# ESP32_sparrow.net
KiCad netlist of a schematic drawn in EAGLE
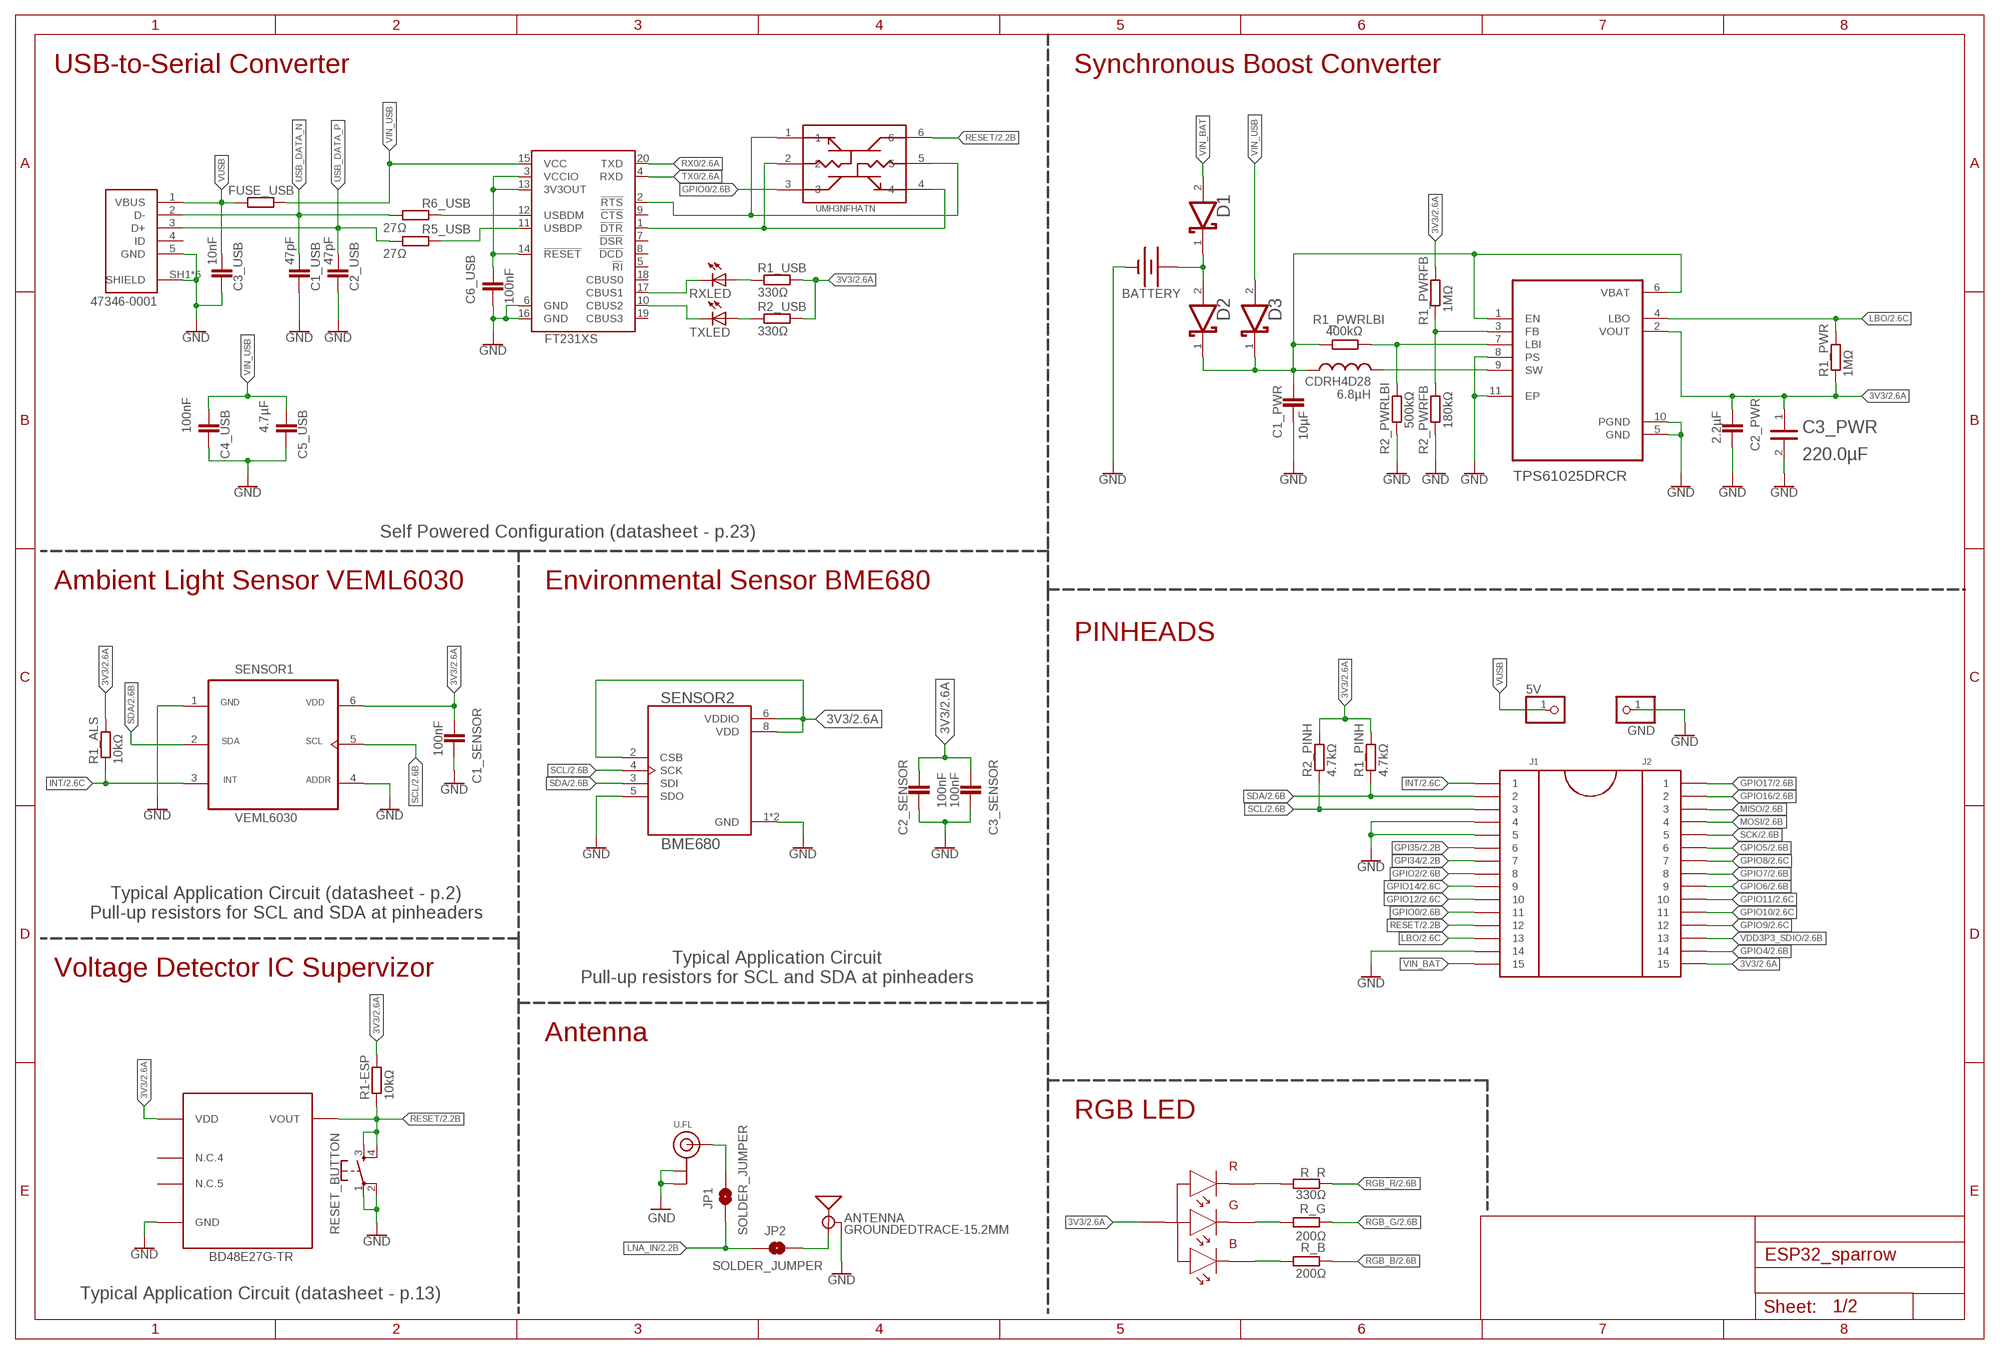
[diagram p0: schematic, sheet 1]
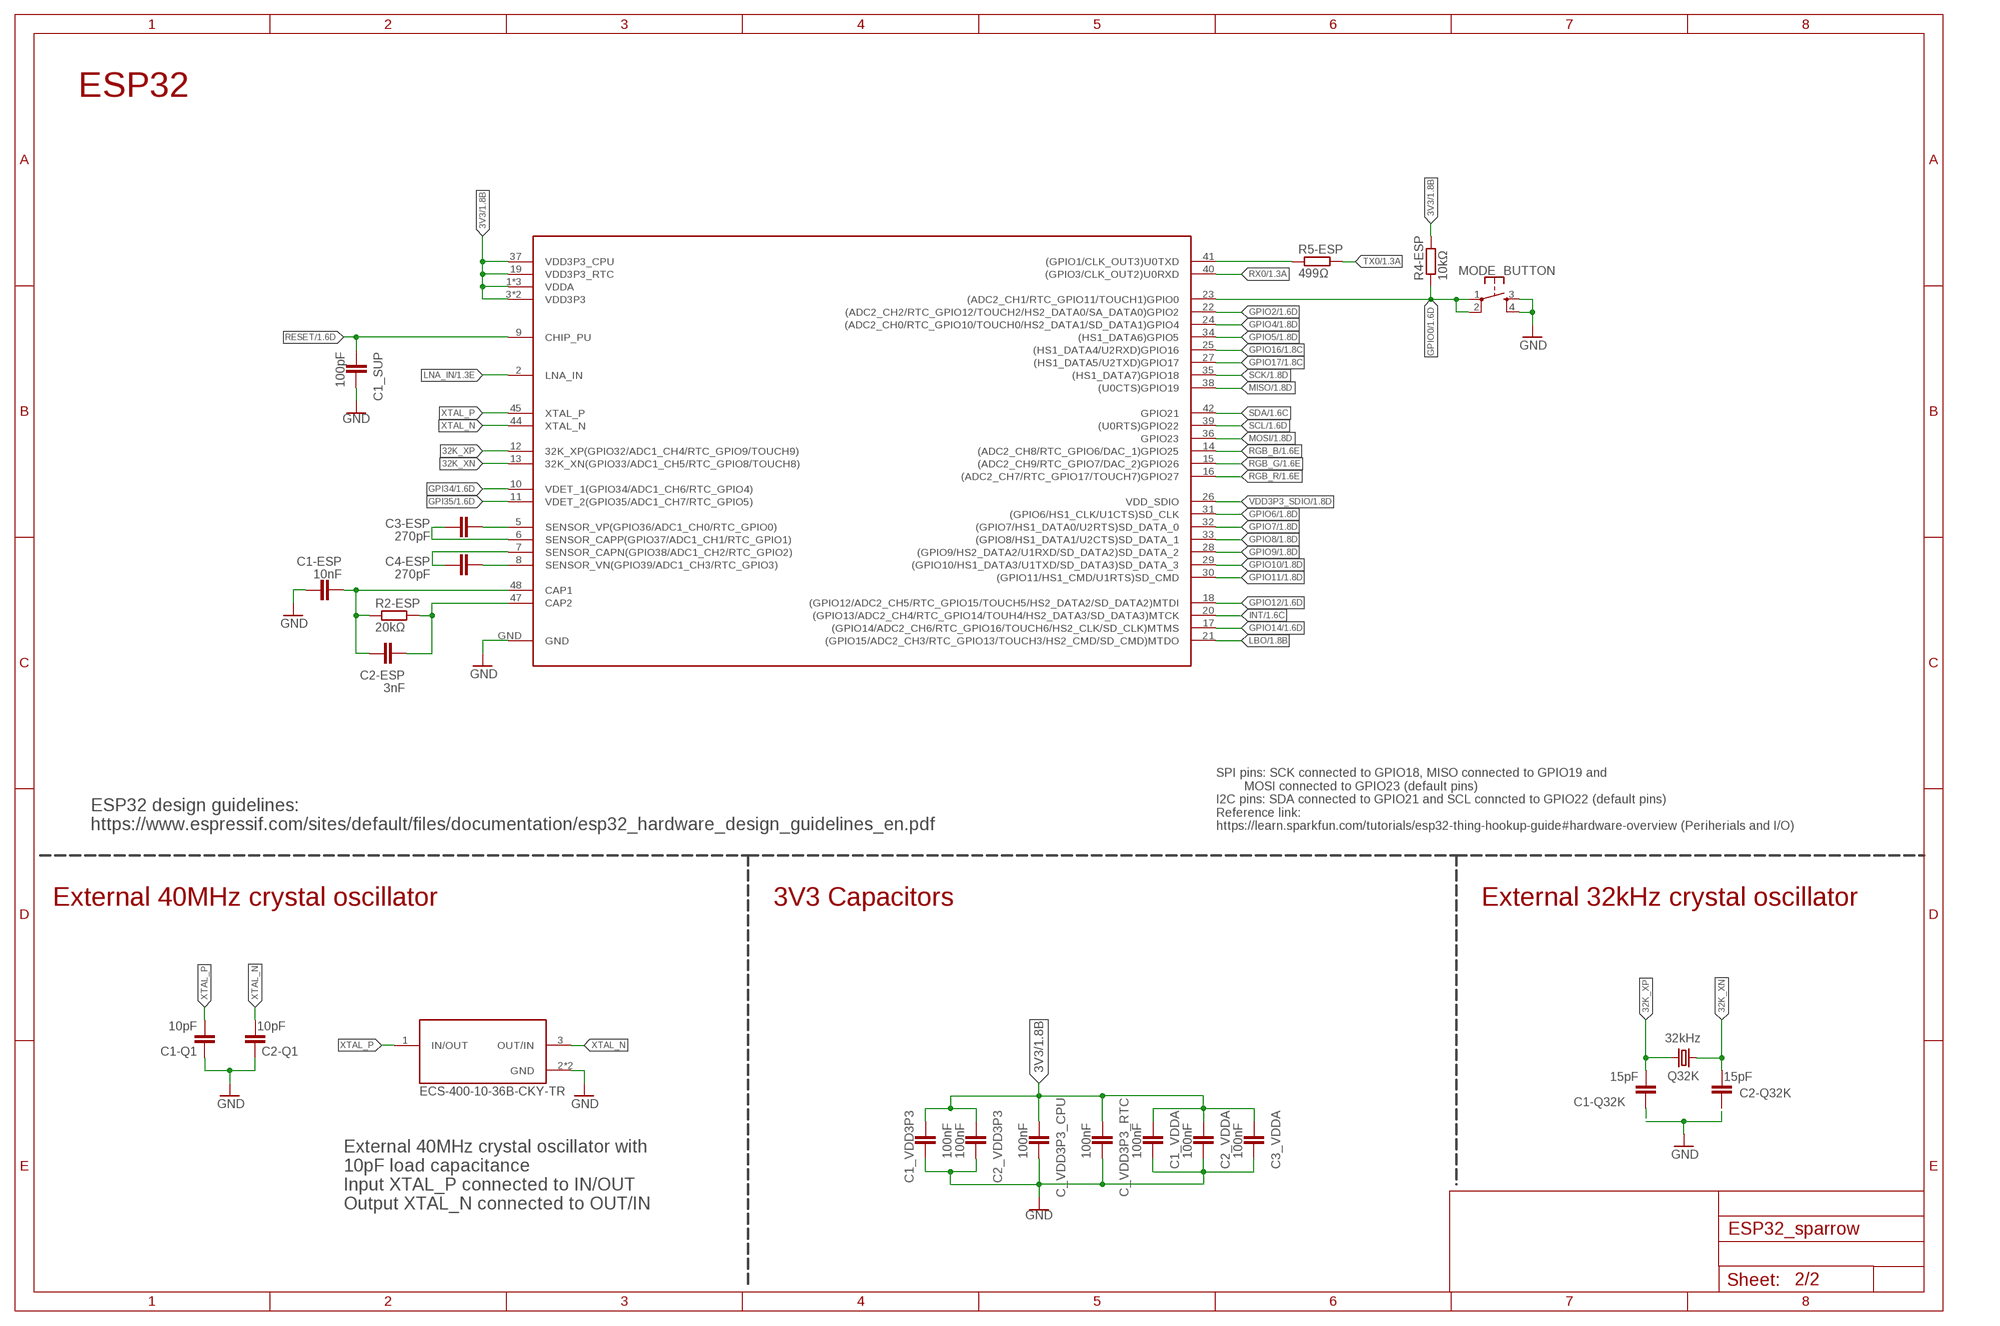
[diagram p1: schematic, sheet 2]

(export (version "E")
  (design (tool "Eeschema 10.0.6"))
  (components
    (comp (ref "C1-ESP")
      (value "10nF")
      (footprint "eagle-import:C0402")
      (libsource (lib "eagle-import") (part "CC0402"))
    )
    (comp (ref "C1-Q1")
      (value "10pF")
      (footprint "eagle-import:C0402")
      (libsource (lib "eagle-import") (part "CC0402"))
    )
    (comp (ref "C1-Q32K")
      (value "15pF")
      (footprint "eagle-import:C0402")
      (libsource (lib "eagle-import") (part "CC0402"))
    )
    (comp (ref "C1_SUP")
      (value "100pF")
      (footprint "eagle-import:C0402")
      (libsource (lib "eagle-import") (part "CC0402"))
    )
    (comp (ref "C1_VDD3P3")
      (value "100nF")
      (footprint "eagle-import:C0402")
      (libsource (lib "eagle-import") (part "CC0402"))
    )
    (comp (ref "C1_VDDA")
      (value "100nF")
      (footprint "eagle-import:C0402")
      (libsource (lib "eagle-import") (part "CC0402"))
    )
    (comp (ref "C2-ESP")
      (value "3nF")
      (footprint "eagle-import:C0402")
      (libsource (lib "eagle-import") (part "CC0402"))
    )
    (comp (ref "C2-Q1")
      (value "10pF")
      (footprint "eagle-import:C0402")
      (libsource (lib "eagle-import") (part "CC0402"))
    )
    (comp (ref "C2-Q32K")
      (value "15pF")
      (footprint "eagle-import:C0402")
      (libsource (lib "eagle-import") (part "CC0402"))
    )
    (comp (ref "C2_VDD3P3")
      (value "100nF")
      (footprint "eagle-import:C0402")
      (libsource (lib "eagle-import") (part "CC0402"))
    )
    (comp (ref "C2_VDDA")
      (value "100nF")
      (footprint "eagle-import:C0402")
      (libsource (lib "eagle-import") (part "CC0402"))
    )
    (comp (ref "C3-ESP")
      (value "270pF")
      (footprint "eagle-import:C0402")
      (libsource (lib "eagle-import") (part "CC0402"))
    )
    (comp (ref "C3_VDDA")
      (value "100nF")
      (footprint "eagle-import:C0402")
      (libsource (lib "eagle-import") (part "CC0402"))
    )
    (comp (ref "C4-ESP")
      (value "270pF")
      (footprint "eagle-import:C0402")
      (libsource (lib "eagle-import") (part "CC0402"))
    )
    (comp (ref "C_VDD3P3_CPU")
      (value "100nF")
      (footprint "eagle-import:C0402")
      (libsource (lib "eagle-import") (part "CC0402"))
    )
    (comp (ref "C_VDD3P3_RTC")
      (value "100nF")
      (footprint "eagle-import:C0402")
      (libsource (lib "eagle-import") (part "CC0402"))
    )
    (comp (ref "MODE_BUTTON")
      (value "MOMENTARY-SWITCH-SPST-2-SMD-4.6X2.8MM")
      (footprint "eagle-import:TACTILE_SWITCH_SMD_4.6X2.8MM")
      (libsource (lib "eagle-import") (part "MOMENTARY-SWITCH-SPST-2-SMD-4.6X2.8MM"))
    )
    (comp (ref "Q32K")
      (value "32kHz")
      (footprint "eagle-import:FC-12M")
      (libsource (lib "eagle-import") (part "FC-12M"))
    )
    (comp (ref "Q40M")
      (value "ECS-400-10-36B-CKY-TR")
      (footprint "eagle-import:XTAL_ECS-163.84-10-36-JGN-TR")
      (fields (field (name "MF") "ECS Inc."))
      (libsource (lib "eagle-import") (part "ECS-400-10-36B-CKY-TR"))
    )
    (comp (ref "R2-ESP")
      (value "20kΩ")
      (footprint "eagle-import:R0402")
      (libsource (lib "eagle-import") (part "RR0402"))
    )
    (comp (ref "R4-ESP")
      (value "10kΩ")
      (footprint "eagle-import:R0402")
      (libsource (lib "eagle-import") (part "RR0402"))
    )
    (comp (ref "R5-ESP")
      (value "499Ω")
      (footprint "eagle-import:R0402")
      (libsource (lib "eagle-import") (part "RR0402"))
    )
    (comp (ref "U$3")
      (value "ESP32-U4WDH")
      (footprint "eagle-import:ESP32-U4WDH")
      (libsource (lib "eagle-import") (part "ESP32-U4WDH"))
    )
    (comp (ref "5V")
      (value "PINHD-1X1")
      (footprint "eagle-import:1X01")
      (libsource (lib "eagle-import") (part "PINHD-1X1"))
    )
    (comp (ref "ANTENNA")
      (value "GROUNDEDTRACE-15.2MM")
      (footprint "eagle-import:TRACE_ANTENNA_2.4GHZ_15.2MM")
      (libsource (lib "eagle-import") (part "ANTENNA-GROUNDEDTRACE-15.2MM"))
    )
    (comp (ref "BATTERY")
      (value "BATTERY-AA")
      (footprint "eagle-import:BATTERY-AA")
      (libsource (lib "eagle-import") (part "BATTERY-AA"))
    )
    (comp (ref "BD48E27G-TR")
      (value "BD48E27G-TR")
      (footprint "eagle-import:SSOP5")
      (libsource (lib "eagle-import") (part "BD48E27G-TR"))
    )
    (comp (ref "C1_PWR")
      (value "10µF")
      (footprint "eagle-import:C0402")
      (libsource (lib "eagle-import") (part "CC0402"))
    )
    (comp (ref "C1_SENSOR")
      (value "100nF")
      (footprint "eagle-import:C0402")
      (libsource (lib "eagle-import") (part "CC0402"))
    )
    (comp (ref "C1_USB")
      (value "47pF")
      (footprint "eagle-import:C0402")
      (libsource (lib "eagle-import") (part "CC0402"))
    )
    (comp (ref "C2_PWR")
      (value "2.2µF")
      (footprint "eagle-import:C0402")
      (libsource (lib "eagle-import") (part "CC0402"))
    )
    (comp (ref "C2_SENSOR")
      (value "100nF")
      (footprint "eagle-import:C0402")
      (libsource (lib "eagle-import") (part "CC0402"))
    )
    (comp (ref "C2_USB")
      (value "47pF")
      (footprint "eagle-import:C0402")
      (libsource (lib "eagle-import") (part "CC0402"))
    )
    (comp (ref "C3_PWR")
      (value "SAMSUNG_ELECTRO-MECHANICS_AMERICA_CL32A227MQVNNNESAMSUNG_ELECTRO-MECHANICS_AMERICA_CL32A227MQVNNNE_0_0")
      (footprint "eagle-import:SAMSUNG_ELECTRO-MECHANICS_AMERICA_CL32A227MQVNNNE_0")
      (fields
        (field (name "DIGIKEY_PART_NUMBER") "1276-3375-1-ND")
        (field (name "MF") "Samsung Electro-Mechanics America")
        (field (name "MPN") "CL32A227MQVNNNE")
      )
      (libsource (lib "eagle-import") (part "SAMSUNG_ELECTRO-MECHANICS_AMERICA_CL32A227MQVNNNESAMSUNG_ELECTRO-MECHANICS_AMERICA_CL32A227MQVNNNE_0_0"))
    )
    (comp (ref "C3_SENSOR")
      (value "100nF")
      (footprint "eagle-import:C0402")
      (libsource (lib "eagle-import") (part "CC0402"))
    )
    (comp (ref "C3_USB")
      (value "10nF")
      (footprint "eagle-import:C0402")
      (libsource (lib "eagle-import") (part "CC0402"))
    )
    (comp (ref "C4_USB")
      (value "100nF")
      (footprint "eagle-import:C0402")
      (libsource (lib "eagle-import") (part "CC0402"))
    )
    (comp (ref "C5_USB")
      (value "4.7µF")
      (footprint "eagle-import:C0402")
      (libsource (lib "eagle-import") (part "CC0402"))
    )
    (comp (ref "C6_USB")
      (value "100nF")
      (footprint "eagle-import:C0402")
      (libsource (lib "eagle-import") (part "CC0402"))
    )
    (comp (ref "CDRH4D28")
      (value "6.8µH")
      (footprint "eagle-import:INDUCTOR_CDRH4")
      (libsource (lib "eagle-import") (part "L_US-CDRH4D28"))
    )
    (comp (ref "CONVERTER")
      (value "TPS61025DRCR")
      (footprint "eagle-import:VREG_V62_16624-01YE")
      (fields (field (name "MF") "Texas Instruments"))
      (libsource (lib "eagle-import") (part "TPS61025DRCR"))
    )
    (comp (ref "D1")
      (value "AVX_SD0805S020S1R0AVX_SD0805S020S1R0_0_0")
      (footprint "eagle-import:AVX_SD0805S020S1R0_0")
      (fields
        (field (name "DIGIKEY_PART_NUMBER") "478-7800-1-ND")
        (field (name "MF") "AVX")
        (field (name "MOUSER_PART_NUMBER") "581-SD0805S020S1R0")
      )
      (libsource (lib "eagle-import") (part "AVX_SD0805S020S1R0AVX_SD0805S020S1R0_0_0"))
    )
    (comp (ref "D2")
      (value "AVX_SD0805S020S1R0AVX_SD0805S020S1R0_0_0")
      (footprint "eagle-import:AVX_SD0805S020S1R0_0")
      (fields
        (field (name "DIGIKEY_PART_NUMBER") "478-7800-1-ND")
        (field (name "MF") "AVX")
        (field (name "MOUSER_PART_NUMBER") "581-SD0805S020S1R0")
      )
      (libsource (lib "eagle-import") (part "AVX_SD0805S020S1R0AVX_SD0805S020S1R0_0_0"))
    )
    (comp (ref "D3")
      (value "AVX_SD0805S020S1R0AVX_SD0805S020S1R0_0_0")
      (footprint "eagle-import:AVX_SD0805S020S1R0_0")
      (fields
        (field (name "DIGIKEY_PART_NUMBER") "478-7800-1-ND")
        (field (name "MF") "AVX")
        (field (name "MOUSER_PART_NUMBER") "581-SD0805S020S1R0")
      )
      (libsource (lib "eagle-import") (part "AVX_SD0805S020S1R0AVX_SD0805S020S1R0_0_0"))
    )
    (comp (ref "FUSE_USB")
      (value "PFMF.050.2")
      (footprint "eagle-import:1812X7R")
      (libsource (lib "eagle-import") (part "R-EU_1812X7R"))
    )
    (comp (ref "GND")
      (value "PINHD-1X1")
      (footprint "eagle-import:1X01")
      (libsource (lib "eagle-import") (part "PINHD-1X1"))
    )
    (comp (ref "J1")
      (value "HEAD15-NOSS")
      (footprint "eagle-import:HEAD15-NOSS")
      (libsource (lib "eagle-import") (part "HEAD15-NOSS"))
    )
    (comp (ref "J2")
      (value "HEAD15-NOSS-1")
      (footprint "eagle-import:HEAD15-NOSS-1")
      (libsource (lib "eagle-import") (part "HEAD15-NOSS-1"))
    )
    (comp (ref "JP1")
      (value "SOLDER_JUMPER")
      (footprint "eagle-import:SMT-JUMPER_2_NO_NO-SILK")
      (libsource (lib "eagle-import") (part "JUMPER-SMT_2_NO_NO-SILK"))
    )
    (comp (ref "JP2")
      (value "SOLDER_JUMPER")
      (footprint "eagle-import:SMT-JUMPER_2_NO_NO-SILK")
      (libsource (lib "eagle-import") (part "JUMPER-SMT_2_NO_NO-SILK"))
    )
    (comp (ref "MOLEX")
      (value "47346-0001")
      (footprint "eagle-import:MOLEX_47346-0001")
      (fields (field (name "MF") "Molex"))
      (libsource (lib "eagle-import") (part "47346-0001"))
    )
    (comp (ref "R1-ESP")
      (value "10kΩ")
      (footprint "eagle-import:R0402")
      (libsource (lib "eagle-import") (part "RR0402"))
    )
    (comp (ref "R1_ALS")
      (value "10kΩ")
      (footprint "eagle-import:R0402")
      (libsource (lib "eagle-import") (part "RR0402"))
    )
    (comp (ref "R1_PINH")
      (value "4.7kΩ")
      (footprint "eagle-import:R0402")
      (libsource (lib "eagle-import") (part "RR0402"))
    )
    (comp (ref "R1_PWR")
      (value "1MΩ")
      (footprint "eagle-import:R0402")
      (libsource (lib "eagle-import") (part "RR0402"))
    )
    (comp (ref "R1_PWRFB")
      (value "1MΩ")
      (footprint "eagle-import:R0402")
      (libsource (lib "eagle-import") (part "RR0402"))
    )
    (comp (ref "R1_PWRLBI")
      (value "400kΩ")
      (footprint "eagle-import:R0402")
      (libsource (lib "eagle-import") (part "RR0402"))
    )
    (comp (ref "R1_USB")
      (value "330Ω")
      (footprint "eagle-import:R0402")
      (libsource (lib "eagle-import") (part "RR0402"))
    )
    (comp (ref "R2_PINH")
      (value "4.7kΩ")
      (footprint "eagle-import:R0402")
      (libsource (lib "eagle-import") (part "RR0402"))
    )
    (comp (ref "R2_PWRFB")
      (value "180kΩ")
      (footprint "eagle-import:R0402")
      (libsource (lib "eagle-import") (part "RR0402"))
    )
    (comp (ref "R2_PWRLBI")
      (value "500kΩ")
      (footprint "eagle-import:R0402")
      (libsource (lib "eagle-import") (part "RR0402"))
    )
    (comp (ref "R2_USB")
      (value "330Ω")
      (footprint "eagle-import:R0402")
      (libsource (lib "eagle-import") (part "RR0402"))
    )
    (comp (ref "R5_USB")
      (value "27Ω")
      (footprint "eagle-import:R0402")
      (libsource (lib "eagle-import") (part "RR0402"))
    )
    (comp (ref "R6_USB")
      (value "27Ω")
      (footprint "eagle-import:R0402")
      (libsource (lib "eagle-import") (part "RR0402"))
    )
    (comp (ref "RESET_BUTTON")
      (value "MOMENTARY-SWITCH-SPST-2-SMD-4.6X2.8MM")
      (footprint "eagle-import:TACTILE_SWITCH_SMD_4.6X2.8MM")
      (libsource (lib "eagle-import") (part "MOMENTARY-SWITCH-SPST-2-SMD-4.6X2.8MM"))
    )
    (comp (ref "RXLED")
      (value "LEDCHIP-LED0603")
      (footprint "eagle-import:CHIP-LED0603")
      (libsource (lib "eagle-import") (part "LEDCHIP-LED0603"))
    )
    (comp (ref "R_B")
      (value "200Ω")
      (footprint "eagle-import:R0402")
      (libsource (lib "eagle-import") (part "eagle-ltspice_217_RR0402"))
    )
    (comp (ref "R_G")
      (value "200Ω")
      (footprint "eagle-import:R0402")
      (libsource (lib "eagle-import") (part "eagle-ltspice_217_RR0402"))
    )
    (comp (ref "R_R")
      (value "330Ω")
      (footprint "eagle-import:R0402")
      (libsource (lib "eagle-import") (part "eagle-ltspice_217_RR0402"))
    )
    (comp (ref "SENSOR1")
      (value "VEML6030")
      (footprint "eagle-import:VISHAY_VEML6030_2X2X0.87")
      (fields (field (name "MF") "Vishay"))
      (libsource (lib "eagle-import") (part "VEML6030"))
    )
    (comp (ref "SENSOR2")
      (value "BME680")
      (footprint "eagle-import:PSON80P300X300X100-8N")
      (fields (field (name "MF") "Bosch Sensortec"))
      (libsource (lib "eagle-import") (part "BME680"))
    )
    (comp (ref "TXLED")
      (value "LEDCHIP-LED0603")
      (footprint "eagle-import:CHIP-LED0603")
      (libsource (lib "eagle-import") (part "LEDCHIP-LED0603"))
    )
    (comp (ref "U$1")
      (value "150202M153130-RGB")
      (footprint "eagle-import:150202M153130")
      (libsource (lib "eagle-import") (part "150202M153130-RGB"))
    )
    (comp (ref "U.FL")
      (value "ANTENNA_U.FL")
      (footprint "eagle-import:U.FL")
      (libsource (lib "eagle-import") (part "ANTENNA_U.FL"))
    )
    (comp (ref "U4")
      (value "FT231XS")
      (footprint "eagle-import:SSOP20_L")
      (libsource (lib "eagle-import") (part "FT231XS"))
    )
    (comp (ref "UMH3NFHATN")
      (value "UMH3NFHATN")
      (footprint "eagle-import:SOP65P210X100-6N")
      (fields (field (name "MF") "Rohm") (field (name "MP") "UMH3N"))
      (libsource (lib "eagle-import") (part "UMH3N"))
    )
  )
  (nets
    (net (code "1") (name "3V3") (class "Default")
      (node (ref "BD48E27G-TR") (pin "P$2") (pinfunction "VDD_P$2") (pintype "bidirectional"))
      (node (ref "C1_SENSOR") (pin "2") (pinfunction "2_2") (pintype "passive"))
      (node (ref "C1_VDD3P3") (pin "2") (pinfunction "2_2") (pintype "passive"))
      (node (ref "C1_VDDA") (pin "2") (pinfunction "2_2") (pintype "passive"))
      (node (ref "C2_PWR") (pin "2") (pinfunction "2_2") (pintype "passive"))
      (node (ref "C2_SENSOR") (pin "2") (pinfunction "2_2") (pintype "passive"))
      (node (ref "C2_VDD3P3") (pin "2") (pinfunction "2_2") (pintype "passive"))
      (node (ref "C2_VDDA") (pin "2") (pinfunction "2_2") (pintype "passive"))
      (node (ref "C3_PWR") (pin "1") (pinfunction "1_1") (pintype "bidirectional"))
      (node (ref "C3_SENSOR") (pin "2") (pinfunction "2_2") (pintype "passive"))
      (node (ref "C3_VDDA") (pin "2") (pinfunction "2_2") (pintype "passive"))
      (node (ref "CONVERTER") (pin "2") (pinfunction "VOUT_2") (pintype "output"))
      (node (ref "C_VDD3P3_CPU") (pin "2") (pinfunction "2_2") (pintype "passive"))
      (node (ref "C_VDD3P3_RTC") (pin "2") (pinfunction "2_2") (pintype "passive"))
      (node (ref "J2") (pin "15") (pinfunction "15_15") (pintype "passive"))
      (node (ref "R1-ESP") (pin "2") (pinfunction "2_2") (pintype "passive"))
      (node (ref "R1_ALS") (pin "2") (pinfunction "2_2") (pintype "passive"))
      (node (ref "R1_PINH") (pin "2") (pinfunction "2_2") (pintype "passive"))
      (node (ref "R1_PWR") (pin "1") (pinfunction "1_1") (pintype "passive"))
      (node (ref "R1_PWRFB") (pin "2") (pinfunction "2_2") (pintype "passive"))
      (node (ref "R1_USB") (pin "2") (pinfunction "2_2") (pintype "passive"))
      (node (ref "R2_PINH") (pin "2") (pinfunction "2_2") (pintype "passive"))
      (node (ref "R2_USB") (pin "2") (pinfunction "2_2") (pintype "passive"))
      (node (ref "R4-ESP") (pin "2") (pinfunction "2_2") (pintype "passive"))
      (node (ref "SENSOR1") (pin "6") (pinfunction "VDD_6") (pintype "power_in"))
      (node (ref "SENSOR2") (pin "2") (pinfunction "CSB_2") (pintype "input"))
      (node (ref "SENSOR2") (pin "6") (pinfunction "VDDIO_6") (pintype "power_in"))
      (node (ref "SENSOR2") (pin "8") (pinfunction "VDD_8") (pintype "power_in"))
      (node (ref "U$1") (pin "P$1") (pinfunction "1_P$1") (pintype "bidirectional"))
      (node (ref "U$3") (pin "1") (pinfunction "VDDA_1") (pintype "bidirectional"))
      (node (ref "U$3") (pin "19") (pinfunction "VDD3P3_RTC_19") (pintype "bidirectional"))
      (node (ref "U$3") (pin "3") (pinfunction "VDD3P3_3") (pintype "bidirectional"))
      (node (ref "U$3") (pin "37") (pinfunction "VDD3P3_CPU_37") (pintype "bidirectional"))
      (node (ref "U$3") (pin "4") (pinfunction "VDD3P3_4") (pintype "bidirectional"))
      (node (ref "U$3") (pin "43") (pinfunction "VDDA_43") (pintype "bidirectional"))
      (node (ref "U$3") (pin "46") (pinfunction "VDDA_46") (pintype "bidirectional"))
    )
    (net (code "2") (name "32K_XN") (class "Default")
      (node (ref "C2-Q32K") (pin "2") (pinfunction "2_2") (pintype "passive"))
      (node (ref "Q32K") (pin "1") (pinfunction "1_1") (pintype "passive"))
      (node (ref "U$3") (pin "13") (pinfunction "32K_XN(GPIO33/ADC1_CH5/RTC_GPIO8/TOUCH8)_13") (pintype "bidirectional"))
    )
    (net (code "3") (name "32K_XP") (class "Default")
      (node (ref "C1-Q32K") (pin "2") (pinfunction "2_2") (pintype "passive"))
      (node (ref "Q32K") (pin "2") (pinfunction "2_2") (pintype "passive"))
      (node (ref "U$3") (pin "12") (pinfunction "32K_XP(GPIO32/ADC1_CH4/RTC_GPIO9/TOUCH9)_12") (pintype "bidirectional"))
    )
    (net (code "4") (name "GND") (class "Default")
      (node (ref "ANTENNA") (pin "GND") (pinfunction "GND_GND") (pintype "bidirectional"))
      (node (ref "BATTERY") (pin "GND@1") (pinfunction "-_GND@1") (pintype "power_in"))
      (node (ref "BD48E27G-TR") (pin "P$3") (pinfunction "GND_P$3") (pintype "bidirectional"))
      (node (ref "C1-ESP") (pin "1") (pinfunction "1_1") (pintype "passive"))
      (node (ref "C1-Q1") (pin "1") (pinfunction "1_1") (pintype "passive"))
      (node (ref "C1-Q32K") (pin "1") (pinfunction "1_1") (pintype "passive"))
      (node (ref "C1_PWR") (pin "1") (pinfunction "1_1") (pintype "passive"))
      (node (ref "C1_SENSOR") (pin "1") (pinfunction "1_1") (pintype "passive"))
      (node (ref "C1_SUP") (pin "1") (pinfunction "1_1") (pintype "passive"))
      (node (ref "C1_USB") (pin "2") (pinfunction "2_2") (pintype "passive"))
      (node (ref "C1_VDD3P3") (pin "1") (pinfunction "1_1") (pintype "passive"))
      (node (ref "C1_VDDA") (pin "1") (pinfunction "1_1") (pintype "passive"))
      (node (ref "C2-Q1") (pin "1") (pinfunction "1_1") (pintype "passive"))
      (node (ref "C2-Q32K") (pin "1") (pinfunction "1_1") (pintype "passive"))
      (node (ref "C2_PWR") (pin "1") (pinfunction "1_1") (pintype "passive"))
      (node (ref "C2_SENSOR") (pin "1") (pinfunction "1_1") (pintype "passive"))
      (node (ref "C2_USB") (pin "2") (pinfunction "2_2") (pintype "passive"))
      (node (ref "C2_VDD3P3") (pin "1") (pinfunction "1_1") (pintype "passive"))
      (node (ref "C2_VDDA") (pin "1") (pinfunction "1_1") (pintype "passive"))
      (node (ref "C3_PWR") (pin "2") (pinfunction "2_2") (pintype "bidirectional"))
      (node (ref "C3_SENSOR") (pin "1") (pinfunction "1_1") (pintype "passive"))
      (node (ref "C3_USB") (pin "2") (pinfunction "2_2") (pintype "passive"))
      (node (ref "C3_VDDA") (pin "1") (pinfunction "1_1") (pintype "passive"))
      (node (ref "C4_USB") (pin "2") (pinfunction "2_2") (pintype "passive"))
      (node (ref "C5_USB") (pin "2") (pinfunction "2_2") (pintype "passive"))
      (node (ref "C6_USB") (pin "2") (pinfunction "2_2") (pintype "passive"))
      (node (ref "CONVERTER") (pin "10") (pinfunction "PGND_10") (pintype "power_in"))
      (node (ref "CONVERTER") (pin "11") (pinfunction "EP_11") (pintype "bidirectional"))
      (node (ref "CONVERTER") (pin "5") (pinfunction "GND_5") (pintype "power_in"))
      (node (ref "CONVERTER") (pin "8") (pinfunction "PS_8") (pintype "input"))
      (node (ref "C_VDD3P3_CPU") (pin "1") (pinfunction "1_1") (pintype "passive"))
      (node (ref "C_VDD3P3_RTC") (pin "1") (pinfunction "1_1") (pintype "passive"))
      (node (ref "GND") (pin "1") (pinfunction "1_1") (pintype "passive"))
      (node (ref "J1") (pin "14") (pinfunction "14_14") (pintype "passive"))
      (node (ref "J1") (pin "4") (pinfunction "4_4") (pintype "passive"))
      (node (ref "J1") (pin "5") (pinfunction "5_5") (pintype "passive"))
      (node (ref "MODE_BUTTON") (pin "3") (pinfunction "3_3") (pintype "passive"))
      (node (ref "MODE_BUTTON") (pin "4") (pinfunction "4_4") (pintype "passive"))
      (node (ref "MOLEX") (pin "5") (pinfunction "GND_5") (pintype "power_in"))
      (node (ref "MOLEX") (pin "SH1") (pinfunction "SHIELD_SH1") (pintype "passive"))
      (node (ref "MOLEX") (pin "SH2") (pinfunction "SHIELD_SH2") (pintype "passive"))
      (node (ref "MOLEX") (pin "SH3") (pinfunction "SHIELD_SH3") (pintype "passive"))
      (node (ref "MOLEX") (pin "SH4") (pinfunction "SHIELD_SH4") (pintype "passive"))
      (node (ref "MOLEX") (pin "SH5") (pinfunction "SHIELD_SH5") (pintype "passive"))
      (node (ref "MOLEX") (pin "SH6") (pinfunction "SHIELD_SH6") (pintype "passive"))
      (node (ref "Q40M") (pin "2") (pinfunction "GND_2") (pintype "power_in"))
      (node (ref "Q40M") (pin "4") (pinfunction "GND_4") (pintype "power_in"))
      (node (ref "R2_PWRFB") (pin "1") (pinfunction "1_1") (pintype "passive"))
      (node (ref "R2_PWRLBI") (pin "1") (pinfunction "1_1") (pintype "passive"))
      (node (ref "RESET_BUTTON") (pin "1") (pinfunction "1_1") (pintype "passive"))
      (node (ref "RESET_BUTTON") (pin "2") (pinfunction "2_2") (pintype "passive"))
      (node (ref "SENSOR1") (pin "1") (pinfunction "GND_1") (pintype "power_in"))
      (node (ref "SENSOR1") (pin "4") (pinfunction "ADDR_4") (pintype "bidirectional"))
      (node (ref "SENSOR2") (pin "1") (pinfunction "GND_1") (pintype "power_in"))
      (node (ref "SENSOR2") (pin "5") (pinfunction "SDO_5") (pintype "bidirectional"))
      (node (ref "SENSOR2") (pin "7") (pinfunction "GND_7") (pintype "power_in"))
      (node (ref "U$3") (pin "GND") (pinfunction "GND_GND") (pintype "bidirectional"))
      (node (ref "U.FL") (pin "1") (pinfunction "GND_1") (pintype "passive"))
      (node (ref "U.FL") (pin "2") (pinfunction "GND_2") (pintype "passive"))
      (node (ref "U4") (pin "16") (pinfunction "GND_16") (pintype "bidirectional"))
      (node (ref "U4") (pin "6") (pinfunction "GND_6") (pintype "bidirectional"))
    )
    (net (code "5") (name "GPI34") (class "Default")
      (node (ref "J1") (pin "7") (pinfunction "7_7") (pintype "passive"))
      (node (ref "U$3") (pin "10") (pinfunction "VDET_1(GPIO34/ADC1_CH6/RTC_GPIO4)_10") (pintype "bidirectional"))
    )
    (net (code "6") (name "GPI35") (class "Default")
      (node (ref "J1") (pin "6") (pinfunction "6_6") (pintype "passive"))
      (node (ref "U$3") (pin "11") (pinfunction "VDET_2(GPIO35/ADC1_CH7/RTC_GPIO5)_11") (pintype "bidirectional"))
    )
    (net (code "7") (name "GPIO0") (class "Default")
      (node (ref "J1") (pin "11") (pinfunction "11_11") (pintype "passive"))
      (node (ref "MODE_BUTTON") (pin "1") (pinfunction "1_1") (pintype "passive"))
      (node (ref "MODE_BUTTON") (pin "2") (pinfunction "2_2") (pintype "passive"))
      (node (ref "R4-ESP") (pin "1") (pinfunction "1_1") (pintype "passive"))
      (node (ref "U$3") (pin "23") (pinfunction "(ADC2_CH1/RTC_GPIO11/TOUCH1)GPIO0_23") (pintype "bidirectional"))
      (node (ref "UMH3NFHATN") (pin "3") (pinfunction "3_3") (pintype "bidirectional"))
    )
    (net (code "8") (name "GPIO2") (class "Default")
      (node (ref "J1") (pin "8") (pinfunction "8_8") (pintype "passive"))
      (node (ref "U$3") (pin "22") (pinfunction "(ADC2_CH2/RTC_GPIO12/TOUCH2/HS2_DATA0/SA_DATA0)GPIO2_22") (pintype "bidirectional"))
    )
    (net (code "9") (name "GPIO4") (class "Default")
      (node (ref "J2") (pin "14") (pinfunction "14_14") (pintype "passive"))
      (node (ref "U$3") (pin "24") (pinfunction "(ADC2_CH0/RTC_GPIO10/TOUCH0/HS2_DATA1/SD_DATA1)GPIO4_24") (pintype "bidirectional"))
    )
    (net (code "10") (name "GPIO5") (class "Default")
      (node (ref "J2") (pin "6") (pinfunction "6_6") (pintype "passive"))
      (node (ref "U$3") (pin "34") (pinfunction "(HS1_DATA6)GPIO5_34") (pintype "bidirectional"))
    )
    (net (code "11") (name "GPIO6") (class "Default")
      (node (ref "J2") (pin "9") (pinfunction "9_9") (pintype "passive"))
      (node (ref "U$3") (pin "31") (pinfunction "(GPIO6/HS1_CLK/U1CTS)SD_CLK_31") (pintype "bidirectional"))
    )
    (net (code "12") (name "GPIO7") (class "Default")
      (node (ref "J2") (pin "8") (pinfunction "8_8") (pintype "passive"))
      (node (ref "U$3") (pin "32") (pinfunction "(GPIO7/HS1_DATA0/U2RTS)SD_DATA_0_32") (pintype "bidirectional"))
    )
    (net (code "13") (name "GPIO8") (class "Default")
      (node (ref "J2") (pin "7") (pinfunction "7_7") (pintype "passive"))
      (node (ref "U$3") (pin "33") (pinfunction "(GPIO8/HS1_DATA1/U2CTS)SD_DATA_1_33") (pintype "bidirectional"))
    )
    (net (code "14") (name "GPIO9") (class "Default")
      (node (ref "J2") (pin "12") (pinfunction "12_12") (pintype "passive"))
      (node (ref "U$3") (pin "28") (pinfunction "(GPIO9/HS2_DATA2/U1RXD/SD_DATA2)SD_DATA_2_28") (pintype "bidirectional"))
    )
    (net (code "15") (name "GPIO10") (class "Default")
      (node (ref "J2") (pin "11") (pinfunction "11_11") (pintype "passive"))
      (node (ref "U$3") (pin "29") (pinfunction "(GPIO10/HS1_DATA3/U1TXD/SD_DATA3)SD_DATA_3_29") (pintype "bidirectional"))
    )
    (net (code "16") (name "GPIO11") (class "Default")
      (node (ref "J2") (pin "10") (pinfunction "10_10") (pintype "passive"))
      (node (ref "U$3") (pin "30") (pinfunction "(GPIO11/HS1_CMD/U1RTS)SD_CMD_30") (pintype "bidirectional"))
    )
    (net (code "17") (name "GPIO12") (class "Default")
      (node (ref "J1") (pin "10") (pinfunction "10_10") (pintype "passive"))
      (node (ref "U$3") (pin "18") (pinfunction "(GPIO12/ADC2_CH5/RTC_GPIO15/TOUCH5/HS2_DATA2/SD_DATA2)MTDI_18") (pintype "bidirectional"))
    )
    (net (code "18") (name "GPIO14") (class "Default")
      (node (ref "J1") (pin "9") (pinfunction "9_9") (pintype "passive"))
      (node (ref "U$3") (pin "17") (pinfunction "(GPIO14/ADC2_CH6/RTC_GPIO16/TOUCH6/HS2_CLK/SD_CLK)MTMS_17") (pintype "bidirectional"))
    )
    (net (code "19") (name "GPIO16") (class "Default")
      (node (ref "J2") (pin "2") (pinfunction "2_2") (pintype "passive"))
      (node (ref "U$3") (pin "25") (pinfunction "(HS1_DATA4/U2RXD)GPIO16_25") (pintype "bidirectional"))
    )
    (net (code "20") (name "GPIO17") (class "Default")
      (node (ref "J2") (pin "1") (pinfunction "1_1") (pintype "passive"))
      (node (ref "U$3") (pin "27") (pinfunction "(HS1_DATA5/U2TXD)GPIO17_27") (pintype "bidirectional"))
    )
    (net (code "21") (name "INT") (class "Default")
      (node (ref "J1") (pin "1") (pinfunction "1_1") (pintype "passive"))
      (node (ref "R1_ALS") (pin "1") (pinfunction "1_1") (pintype "passive"))
      (node (ref "SENSOR1") (pin "3") (pinfunction "INT_3") (pintype "output"))
      (node (ref "U$3") (pin "20") (pinfunction "(GPIO13/ADC2_CH4/RTC_GPIO14/TOUH4/HS2_DATA3/SD_DATA3)MTCK_20") (pintype "bidirectional"))
    )
    (net (code "22") (name "LBO") (class "Default")
      (node (ref "CONVERTER") (pin "4") (pinfunction "LBO_4") (pintype "output"))
      (node (ref "J1") (pin "13") (pinfunction "13_13") (pintype "passive"))
      (node (ref "R1_PWR") (pin "2") (pinfunction "2_2") (pintype "passive"))
      (node (ref "U$3") (pin "21") (pinfunction "(GPIO15/ADC2_CH3/RTC_GPIO13/TOUCH3/HS2_CMD/SD_CMD)MTDO_21") (pintype "bidirectional"))
    )
    (net (code "23") (name "LNA_IN") (class "Default")
      (node (ref "JP1") (pin "1") (pinfunction "1_1") (pintype "passive"))
      (node (ref "JP2") (pin "1") (pinfunction "1_1") (pintype "passive"))
      (node (ref "U$3") (pin "2") (pinfunction "LNA_IN_2") (pintype "bidirectional"))
    )
    (net (code "24") (name "MISO") (class "Default")
      (node (ref "J2") (pin "3") (pinfunction "3_3") (pintype "passive"))
      (node (ref "U$3") (pin "38") (pinfunction "(U0CTS)GPIO19_38") (pintype "bidirectional"))
    )
    (net (code "25") (name "MOSI") (class "Default")
      (node (ref "J2") (pin "4") (pinfunction "4_4") (pintype "passive"))
      (node (ref "U$3") (pin "36") (pinfunction "GPIO23_36") (pintype "bidirectional"))
    )
    (net (code "26") (name "Net-(ANTENNA-SIGNAL)") (class "Default")
      (node (ref "ANTENNA") (pin "ANT") (pinfunction "SIGNAL_ANT") (pintype "bidirectional"))
      (node (ref "JP2") (pin "2") (pinfunction "2_2") (pintype "passive"))
    )
    (net (code "27") (name "Net-(BATTERY-+)") (class "Default")
      (node (ref "BATTERY") (pin "PWR@1") (pinfunction "+_PWR@1") (pintype "power_in"))
      (node (ref "D1") (pin "1") (pinfunction "CATHODE_1") (pintype "bidirectional"))
      (node (ref "D2") (pin "2") (pinfunction "ANODE_2") (pintype "bidirectional"))
    )
    (net (code "28") (name "Net-(CONVERTER-EN)") (class "Default")
      (node (ref "C1_PWR") (pin "2") (pinfunction "2_2") (pintype "passive"))
      (node (ref "CDRH4D28") (pin "1") (pinfunction "1_1") (pintype "passive"))
      (node (ref "CONVERTER") (pin "1") (pinfunction "EN_1") (pintype "input"))
      (node (ref "CONVERTER") (pin "6") (pinfunction "VBAT_6") (pintype "power_in"))
      (node (ref "D2") (pin "1") (pinfunction "CATHODE_1") (pintype "bidirectional"))
      (node (ref "D3") (pin "1") (pinfunction "CATHODE_1") (pintype "bidirectional"))
      (node (ref "R1_PWRLBI") (pin "1") (pinfunction "1_1") (pintype "passive"))
    )
    (net (code "29") (name "Net-(CONVERTER-FB)") (class "Default")
      (node (ref "CONVERTER") (pin "3") (pinfunction "FB_3") (pintype "input"))
      (node (ref "R1_PWRFB") (pin "1") (pinfunction "1_1") (pintype "passive"))
      (node (ref "R2_PWRFB") (pin "2") (pinfunction "2_2") (pintype "passive"))
    )
    (net (code "30") (name "Net-(CONVERTER-LBI)") (class "Default")
      (node (ref "CONVERTER") (pin "7") (pinfunction "LBI_7") (pintype "input"))
      (node (ref "R1_PWRLBI") (pin "2") (pinfunction "2_2") (pintype "passive"))
      (node (ref "R2_PWRLBI") (pin "2") (pinfunction "2_2") (pintype "passive"))
    )
    (net (code "31") (name "Net-(CONVERTER-SW)") (class "Default")
      (node (ref "CDRH4D28") (pin "2") (pinfunction "2_2") (pintype "passive"))
      (node (ref "CONVERTER") (pin "9") (pinfunction "SW_9") (pintype "input"))
    )
    (net (code "32") (name "Net-(R1_USB-Pad1)") (class "Default")
      (node (ref "R1_USB") (pin "1") (pinfunction "1_1") (pintype "passive"))
      (node (ref "RXLED") (pin "A") (pinfunction "A_A") (pintype "passive"))
    )
    (net (code "33") (name "Net-(R2_USB-Pad1)") (class "Default")
      (node (ref "R2_USB") (pin "1") (pinfunction "1_1") (pintype "passive"))
      (node (ref "TXLED") (pin "A") (pinfunction "A_A") (pintype "passive"))
    )
    (net (code "34") (name "Net-(U$1-2)") (class "Default")
      (node (ref "R_R") (pin "2") (pinfunction "2_2") (pintype "passive"))
      (node (ref "U$1") (pin "P$2") (pinfunction "2_P$2") (pintype "bidirectional"))
    )
    (net (code "35") (name "Net-(U$1-3)") (class "Default")
      (node (ref "R_G") (pin "2") (pinfunction "2_2") (pintype "passive"))
      (node (ref "U$1") (pin "P$3") (pinfunction "3_P$3") (pintype "bidirectional"))
    )
    (net (code "36") (name "Net-(U$1-4)") (class "Default")
      (node (ref "R_B") (pin "2") (pinfunction "2_2") (pintype "passive"))
      (node (ref "U$1") (pin "P$4") (pinfunction "4_P$4") (pintype "bidirectional"))
    )
    (net (code "37") (name "Net-(U$3-(GPIO1{slash}CLK_OUT3)U0TXD)") (class "Default")
      (node (ref "R5-ESP") (pin "1") (pinfunction "1_1") (pintype "passive"))
      (node (ref "U$3") (pin "41") (pinfunction "(GPIO1/CLK_OUT3)U0TXD_41") (pintype "bidirectional"))
    )
    (net (code "38") (name "Net-(U$3-CAP1)") (class "Default")
      (node (ref "C1-ESP") (pin "2") (pinfunction "2_2") (pintype "passive"))
      (node (ref "C2-ESP") (pin "1") (pinfunction "1_1") (pintype "passive"))
      (node (ref "R2-ESP") (pin "1") (pinfunction "1_1") (pintype "passive"))
      (node (ref "U$3") (pin "48") (pinfunction "CAP1_48") (pintype "bidirectional"))
    )
    (net (code "39") (name "Net-(U$3-CAP2)") (class "Default")
      (node (ref "C2-ESP") (pin "2") (pinfunction "2_2") (pintype "passive"))
      (node (ref "R2-ESP") (pin "2") (pinfunction "2_2") (pintype "passive"))
      (node (ref "U$3") (pin "47") (pinfunction "CAP2_47") (pintype "bidirectional"))
    )
    (net (code "40") (name "Net-(U$3-SENSOR_CAPN(GPIO38{slash}ADC1_CH2{slash}RTC_GPIO2))") (class "Default")
      (node (ref "C4-ESP") (pin "1") (pinfunction "1_1") (pintype "passive"))
      (node (ref "U$3") (pin "7") (pinfunction "SENSOR_CAPN(GPIO38/ADC1_CH2/RTC_GPIO2)_7") (pintype "bidirectional"))
    )
    (net (code "41") (name "Net-(U$3-SENSOR_CAPP(GPIO37{slash}ADC1_CH1{slash}RTC_GPIO1))") (class "Default")
      (node (ref "C3-ESP") (pin "1") (pinfunction "1_1") (pintype "passive"))
      (node (ref "U$3") (pin "6") (pinfunction "SENSOR_CAPP(GPIO37/ADC1_CH1/RTC_GPIO1)_6") (pintype "bidirectional"))
    )
    (net (code "42") (name "Net-(U$3-SENSOR_VN(GPIO39{slash}ADC1_CH3{slash}RTC_GPIO3))") (class "Default")
      (node (ref "C4-ESP") (pin "2") (pinfunction "2_2") (pintype "passive"))
      (node (ref "U$3") (pin "8") (pinfunction "SENSOR_VN(GPIO39/ADC1_CH3/RTC_GPIO3)_8") (pintype "bidirectional"))
    )
    (net (code "43") (name "Net-(U$3-SENSOR_VP(GPIO36{slash}ADC1_CH0{slash}RTC_GPIO0))") (class "Default")
      (node (ref "C3-ESP") (pin "2") (pinfunction "2_2") (pintype "passive"))
      (node (ref "U$3") (pin "5") (pinfunction "SENSOR_VP(GPIO36/ADC1_CH0/RTC_GPIO0)_5") (pintype "bidirectional"))
    )
    (net (code "44") (name "Net-(U.FL-SIGNAL)") (class "Default")
      (node (ref "JP1") (pin "2") (pinfunction "2_2") (pintype "passive"))
      (node (ref "U.FL") (pin "3") (pinfunction "SIGNAL_3") (pintype "passive"))
    )
    (net (code "45") (name "Net-(U4-3V3OUT)") (class "Default")
      (node (ref "C6_USB") (pin "1") (pinfunction "1_1") (pintype "passive"))
      (node (ref "U4") (pin "13") (pinfunction "3V3OUT_13") (pintype "bidirectional"))
      (node (ref "U4") (pin "14") (pinfunction "~{RESET}_14") (pintype "bidirectional"))
      (node (ref "U4") (pin "3") (pinfunction "VCCIO_3") (pintype "bidirectional"))
    )
    (net (code "46") (name "Net-(U4-CBUS1)") (class "Default")
      (node (ref "RXLED") (pin "C") (pinfunction "C_C") (pintype "passive"))
      (node (ref "U4") (pin "17") (pinfunction "CBUS1_17") (pintype "bidirectional"))
    )
    (net (code "47") (name "Net-(U4-CBUS2)") (class "Default")
      (node (ref "TXLED") (pin "C") (pinfunction "C_C") (pintype "passive"))
      (node (ref "U4") (pin "10") (pinfunction "CBUS2_10") (pintype "bidirectional"))
    )
    (net (code "48") (name "Net-(U4-USBDM)") (class "Default")
      (node (ref "R6_USB") (pin "2") (pinfunction "2_2") (pintype "passive"))
      (node (ref "U4") (pin "12") (pinfunction "USBDM_12") (pintype "bidirectional"))
    )
    (net (code "49") (name "Net-(U4-USBDP)") (class "Default")
      (node (ref "R5_USB") (pin "2") (pinfunction "2_2") (pintype "passive"))
      (node (ref "U4") (pin "11") (pinfunction "USBDP_11") (pintype "bidirectional"))
    )
    (net (code "50") (name "Net-(U4-~{DTR})") (class "Default")
      (node (ref "U4") (pin "1") (pinfunction "~{DTR}_1") (pintype "bidirectional"))
      (node (ref "UMH3NFHATN") (pin "2") (pinfunction "2_2") (pintype "bidirectional"))
      (node (ref "UMH3NFHATN") (pin "4") (pinfunction "4_4") (pintype "bidirectional"))
    )
    (net (code "51") (name "Net-(U4-~{RTS})") (class "Default")
      (node (ref "U4") (pin "2") (pinfunction "~{RTS}_2") (pintype "bidirectional"))
      (node (ref "UMH3NFHATN") (pin "1") (pinfunction "1_1") (pintype "bidirectional"))
      (node (ref "UMH3NFHATN") (pin "5") (pinfunction "5_5") (pintype "bidirectional"))
    )
    (net (code "52") (name "RESET") (class "Default")
      (node (ref "BD48E27G-TR") (pin "P$1") (pinfunction "VOUT_P$1") (pintype "bidirectional"))
      (node (ref "C1_SUP") (pin "2") (pinfunction "2_2") (pintype "passive"))
      (node (ref "J1") (pin "12") (pinfunction "12_12") (pintype "passive"))
      (node (ref "R1-ESP") (pin "1") (pinfunction "1_1") (pintype "passive"))
      (node (ref "RESET_BUTTON") (pin "3") (pinfunction "3_3") (pintype "passive"))
      (node (ref "RESET_BUTTON") (pin "4") (pinfunction "4_4") (pintype "passive"))
      (node (ref "U$3") (pin "9") (pinfunction "CHIP_PU_9") (pintype "bidirectional"))
      (node (ref "UMH3NFHATN") (pin "6") (pinfunction "6_6") (pintype "bidirectional"))
    )
    (net (code "53") (name "RGB_B") (class "Default")
      (node (ref "R_B") (pin "1") (pinfunction "1_1") (pintype "passive"))
      (node (ref "U$3") (pin "14") (pinfunction "(ADC2_CH8/RTC_GPIO6/DAC_1)GPIO25_14") (pintype "bidirectional"))
    )
    (net (code "54") (name "RGB_G") (class "Default")
      (node (ref "R_G") (pin "1") (pinfunction "1_1") (pintype "passive"))
      (node (ref "U$3") (pin "15") (pinfunction "(ADC2_CH9/RTC_GPIO7/DAC_2)GPIO26_15") (pintype "bidirectional"))
    )
    (net (code "55") (name "RGB_R") (class "Default")
      (node (ref "R_R") (pin "1") (pinfunction "1_1") (pintype "passive"))
      (node (ref "U$3") (pin "16") (pinfunction "(ADC2_CH7/RTC_GPIO17/TOUCH7)GPIO27_16") (pintype "bidirectional"))
    )
    (net (code "56") (name "RX0") (class "Default")
      (node (ref "U$3") (pin "40") (pinfunction "(GPIO3/CLK_OUT2)U0RXD_40") (pintype "bidirectional"))
      (node (ref "U4") (pin "20") (pinfunction "TXD_20") (pintype "bidirectional"))
    )
    (net (code "57") (name "SCK") (class "Default")
      (node (ref "J2") (pin "5") (pinfunction "5_5") (pintype "passive"))
      (node (ref "U$3") (pin "35") (pinfunction "(HS1_DATA7)GPIO18_35") (pintype "bidirectional"))
    )
    (net (code "58") (name "SCL") (class "Default")
      (node (ref "J1") (pin "3") (pinfunction "3_3") (pintype "passive"))
      (node (ref "R2_PINH") (pin "1") (pinfunction "1_1") (pintype "passive"))
      (node (ref "SENSOR1") (pin "5") (pinfunction "SCL_5") (pintype "input"))
      (node (ref "SENSOR2") (pin "4") (pinfunction "SCK_4") (pintype "input"))
      (node (ref "U$3") (pin "39") (pinfunction "(U0RTS)GPIO22_39") (pintype "bidirectional"))
    )
    (net (code "59") (name "SDA") (class "Default")
      (node (ref "J1") (pin "2") (pinfunction "2_2") (pintype "passive"))
      (node (ref "R1_PINH") (pin "1") (pinfunction "1_1") (pintype "passive"))
      (node (ref "SENSOR1") (pin "2") (pinfunction "SDA_2") (pintype "bidirectional"))
      (node (ref "SENSOR2") (pin "3") (pinfunction "SDI_3") (pintype "bidirectional"))
      (node (ref "U$3") (pin "42") (pinfunction "GPIO21_42") (pintype "bidirectional"))
    )
    (net (code "60") (name "TX0") (class "Default")
      (node (ref "R5-ESP") (pin "2") (pinfunction "2_2") (pintype "passive"))
      (node (ref "U4") (pin "4") (pinfunction "RXD_4") (pintype "bidirectional"))
    )
    (net (code "61") (name "USB_DATA_N") (class "Default")
      (node (ref "C1_USB") (pin "1") (pinfunction "1_1") (pintype "passive"))
      (node (ref "MOLEX") (pin "2") (pinfunction "D-_2") (pintype "bidirectional"))
      (node (ref "R6_USB") (pin "1") (pinfunction "1_1") (pintype "passive"))
    )
    (net (code "62") (name "USB_DATA_P") (class "Default")
      (node (ref "C2_USB") (pin "1") (pinfunction "1_1") (pintype "passive"))
      (node (ref "MOLEX") (pin "3") (pinfunction "D+_3") (pintype "bidirectional"))
      (node (ref "R5_USB") (pin "1") (pinfunction "1_1") (pintype "passive"))
    )
    (net (code "63") (name "VDD3P3_SDIO") (class "Default")
      (node (ref "J2") (pin "13") (pinfunction "13_13") (pintype "passive"))
      (node (ref "U$3") (pin "26") (pinfunction "VDD_SDIO_26") (pintype "bidirectional"))
    )
    (net (code "64") (name "VIN_BAT") (class "Default")
      (node (ref "D1") (pin "2") (pinfunction "ANODE_2") (pintype "bidirectional"))
      (node (ref "J1") (pin "15") (pinfunction "15_15") (pintype "passive"))
    )
    (net (code "65") (name "VIN_USB") (class "Default")
      (node (ref "C4_USB") (pin "1") (pinfunction "1_1") (pintype "passive"))
      (node (ref "C5_USB") (pin "1") (pinfunction "1_1") (pintype "passive"))
      (node (ref "D3") (pin "2") (pinfunction "ANODE_2") (pintype "bidirectional"))
      (node (ref "FUSE_USB") (pin "2") (pinfunction "2_2") (pintype "passive"))
      (node (ref "U4") (pin "15") (pinfunction "VCC_15") (pintype "bidirectional"))
    )
    (net (code "66") (name "VUSB") (class "Default")
      (node (ref "5V") (pin "1") (pinfunction "1_1") (pintype "passive"))
      (node (ref "C3_USB") (pin "1") (pinfunction "1_1") (pintype "passive"))
      (node (ref "FUSE_USB") (pin "1") (pinfunction "1_1") (pintype "passive"))
      (node (ref "MOLEX") (pin "1") (pinfunction "VBUS_1") (pintype "power_in"))
    )
    (net (code "67") (name "XTAL_N") (class "Default")
      (node (ref "C2-Q1") (pin "2") (pinfunction "2_2") (pintype "passive"))
      (node (ref "Q40M") (pin "3") (pinfunction "OUT/IN_3") (pintype "bidirectional"))
      (node (ref "U$3") (pin "44") (pinfunction "XTAL_N_44") (pintype "bidirectional"))
    )
    (net (code "68") (name "XTAL_P") (class "Default")
      (node (ref "C1-Q1") (pin "2") (pinfunction "2_2") (pintype "passive"))
      (node (ref "Q40M") (pin "1") (pinfunction "IN/OUT_1") (pintype "bidirectional"))
      (node (ref "U$3") (pin "45") (pinfunction "XTAL_P_45") (pintype "bidirectional"))
    )
    (net (code "69") (name "unconnected-(BD48E27G-TR-N.C.4-PadP$4)") (class "Default")
      (node (ref "BD48E27G-TR") (pin "P$4") (pinfunction "N.C.4_P$4") (pintype "bidirectional"))
    )
    (net (code "70") (name "unconnected-(BD48E27G-TR-N.C.5-PadP$5)") (class "Default")
      (node (ref "BD48E27G-TR") (pin "P$5") (pinfunction "N.C.5_P$5") (pintype "bidirectional"))
    )
    (net (code "71") (name "unconnected-(MOLEX-ID-Pad4)") (class "Default")
      (node (ref "MOLEX") (pin "4") (pinfunction "ID_4") (pintype "passive"))
    )
    (net (code "72") (name "unconnected-(U4-CBUS0-Pad18)") (class "Default")
      (node (ref "U4") (pin "18") (pinfunction "CBUS0_18") (pintype "bidirectional"))
    )
    (net (code "73") (name "unconnected-(U4-CBUS3-Pad19)") (class "Default")
      (node (ref "U4") (pin "19") (pinfunction "CBUS3_19") (pintype "bidirectional"))
    )
    (net (code "74") (name "unconnected-(U4-~{CTS}-Pad9)") (class "Default")
      (node (ref "U4") (pin "9") (pinfunction "~{CTS}_9") (pintype "bidirectional"))
    )
    (net (code "75") (name "unconnected-(U4-~{DCD}-Pad8)") (class "Default")
      (node (ref "U4") (pin "8") (pinfunction "~{DCD}_8") (pintype "bidirectional"))
    )
    (net (code "76") (name "unconnected-(U4-~{DSR}-Pad7)") (class "Default")
      (node (ref "U4") (pin "7") (pinfunction "~{DSR}_7") (pintype "bidirectional"))
    )
    (net (code "77") (name "unconnected-(U4-~{RI}-Pad5)") (class "Default")
      (node (ref "U4") (pin "5") (pinfunction "~{RI}_5") (pintype "bidirectional"))
    )
  )
)
